# Power.net
KiCad netlist of a schematic drawn in Altium Designer
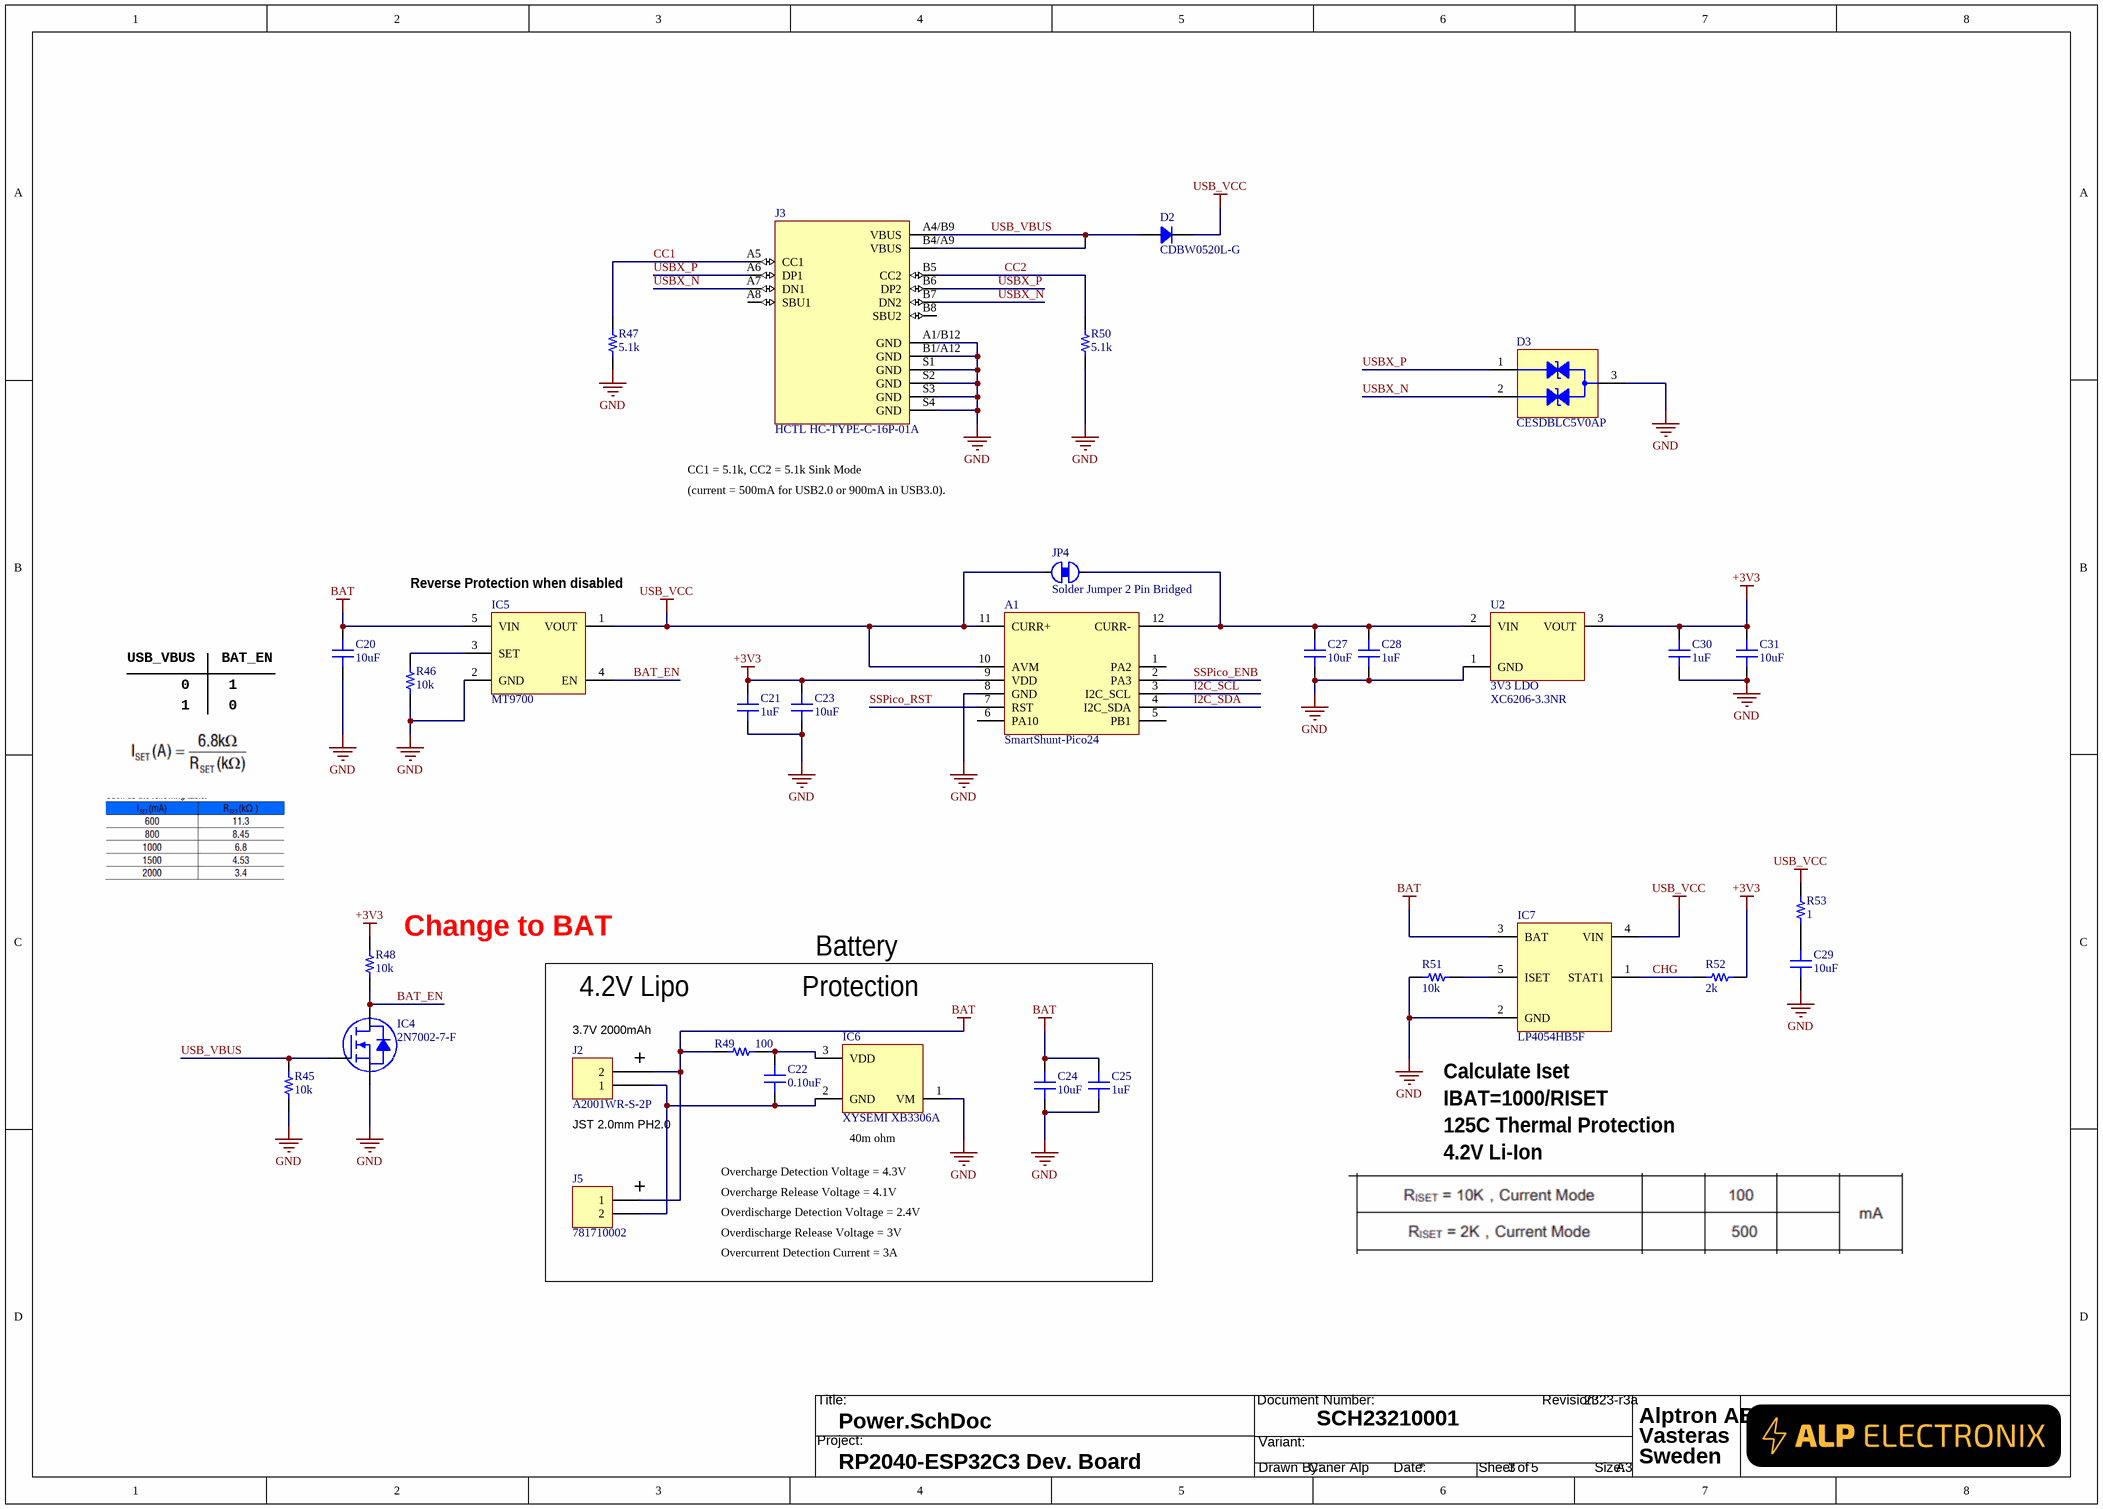
[diagram p0: Power.SchDoc]

(export (version "E")
  (design (tool "Eeschema 10.0.6"))
  (components
    (comp (ref "A1")
      (value "SmartShunt-Pico24")
      (footprint "RP2040_ESP32-C3 Dev Board PCB Lib:SmartShunt-Pico24")
      (description "Current Measurement Module")
      (libsource (lib "RP2040_ESP32-C3 Dev Board SCH Lib") (part "SmartShunt-Pico24"))
    )
    (comp (ref "C20")
      (value "10uF")
      (footprint "CAP 0603/1608")
      (description "CAP CER 10UF 6.3V X5R 0603")
      (fields
        (field (name "PART NUMBER") "GRM188R60J106ME47D")
        (field (name "MANUFACTURER") "Murata Electronics North America")
      )
      (libsource (lib "Celestial Library Database") (part "Capacitor"))
    )
    (comp (ref "C21")
      (value "1uF")
      (footprint "CAP 0402/1005")
      (description "CAP CER 1UF 6.3V X7R 0402")
      (fields
        (field (name "PART NUMBER") "GRM155R70J105KA12D")
        (field (name "MANUFACTURER") "Murata Electronics North America")
      )
      (libsource (lib "Celestial Library Database") (part "Capacitor"))
    )
    (comp (ref "C22")
      (value "0.10uF")
      (footprint "CAP 0402/1005")
      (description "CAP CER 0.1UF 10V X5R 0402")
      (fields (field (name "PART NUMBER") "LMK105BJ104KV-F") (field (name "MANUFACTURER") "Taiyo Yuden"))
      (libsource (lib "Celestial Library Database") (part "Capacitor"))
    )
    (comp (ref "C23")
      (value "10uF")
      (footprint "CAP 0603/1608")
      (description "CAP CER 10UF 6.3V X5R 0603")
      (fields
        (field (name "PART NUMBER") "GRM188R60J106ME47D")
        (field (name "MANUFACTURER") "Murata Electronics North America")
      )
      (libsource (lib "Celestial Library Database") (part "Capacitor"))
    )
    (comp (ref "C24")
      (value "10uF")
      (footprint "CAP 0603/1608")
      (description "CAP CER 10UF 6.3V X5R 0603")
      (fields
        (field (name "PART NUMBER") "GRM188R60J106ME47D")
        (field (name "MANUFACTURER") "Murata Electronics North America")
      )
      (libsource (lib "Celestial Library Database") (part "Capacitor"))
    )
    (comp (ref "C25")
      (value "1uF")
      (footprint "CAP 0402/1005")
      (description "CAP CER 1UF 6.3V X7R 0402")
      (fields
        (field (name "PART NUMBER") "GRM155R70J105KA12D")
        (field (name "MANUFACTURER") "Murata Electronics North America")
      )
      (libsource (lib "Celestial Library Database") (part "Capacitor"))
    )
    (comp (ref "C27")
      (value "10uF")
      (footprint "CAP 0603/1608")
      (description "CAP CER 10UF 6.3V X5R 0603")
      (fields
        (field (name "PART NUMBER") "GRM188R60J106ME47D")
        (field (name "MANUFACTURER") "Murata Electronics North America")
      )
      (libsource (lib "Celestial Library Database") (part "Capacitor"))
    )
    (comp (ref "C28")
      (value "1uF")
      (footprint "CAP 0402/1005")
      (description "CAP CER 1UF 6.3V X7R 0402")
      (fields
        (field (name "PART NUMBER") "GRM155R70J105KA12D")
        (field (name "MANUFACTURER") "Murata Electronics North America")
      )
      (libsource (lib "Celestial Library Database") (part "Capacitor"))
    )
    (comp (ref "C29")
      (value "10uF")
      (footprint "CAP 0603/1608")
      (description "CAP CER 10UF 6.3V X5R 0603")
      (fields
        (field (name "PART NUMBER") "GRM188R60J106ME47D")
        (field (name "MANUFACTURER") "Murata Electronics North America")
      )
      (libsource (lib "Celestial Library Database") (part "Capacitor"))
    )
    (comp (ref "C30")
      (value "1uF")
      (footprint "CAP 0402/1005")
      (description "CAP CER 1UF 6.3V X7R 0402")
      (fields
        (field (name "PART NUMBER") "GRM155R70J105KA12D")
        (field (name "MANUFACTURER") "Murata Electronics North America")
      )
      (libsource (lib "Celestial Library Database") (part "Capacitor"))
    )
    (comp (ref "C31")
      (value "10uF")
      (footprint "CAP 0603/1608")
      (description "CAP CER 10UF 6.3V X5R 0603")
      (fields
        (field (name "PART NUMBER") "GRM188R60J106ME47D")
        (field (name "MANUFACTURER") "Murata Electronics North America")
      )
      (libsource (lib "Celestial Library Database") (part "Capacitor"))
    )
    (comp (ref "D2")
      (value "CDBW0520L-G")
      (footprint "SOD-123")
      (description "DIODE SCHOTTKY 20V 500MA SOD123")
      (fields (field (name "MANUFACTURER") "Comchip Technology"))
      (libsource (lib "Celestial Altium Library - altium_library") (part "Diode"))
    )
    (comp (ref "D3")
      (value "CESDBLC5V0AP")
      (footprint "ON SEMI SOT-23-3")
      (description "TVS DIODE 24V 44V SOT23-3")
      (fields (field (name "MANUFACTURER") "ON Semiconductor"))
      (libsource (lib "Celestial Altium Library - altium_library") (part "ON SEMI SOT-23-3"))
    )
    (comp (ref "IC4")
      (value "2N7002-7-F")
      (footprint "DIODES SOT-23-3")
      (description "MOSFET N-CH 60V 115MA SOT23-3")
      (fields (field (name "MANUFACTURER") "Diodes Incorporated"))
      (libsource (lib "Celestial Library Database") (part "DIODES INC MOSFET N-CH SOT-23-3"))
    )
    (comp (ref "IC5")
      (value "MT9700")
      (footprint "RP2040_ESP32-C3 Dev Board PCB Lib:DIODES SOT-23-5 W5")
      (description "SOT-23-5 Power Distribution Switches ROHS")
      (libsource (lib "RP2040_ESP32-C3 Dev Board SCH Lib") (part "MT9700"))
    )
    (comp (ref "IC6")
      (value "XYSEMI XB3306A")
      (footprint "DIODES SOT-23-3")
      (description "IC LITHIUM BATT PROTECT SOT23-3")
      (fields (field (name "MANUFACTURER") "XYSEMI"))
      (libsource (lib "Celestial Library Database") (part "XYSEMI XB3306A"))
    )
    (comp (ref "IC7")
      (value "LP4054HB5F")
      (footprint "RP2040_ESP32-C3 Dev Board PCB Lib:DIODES SOT-23-5 W5")
      (description "600mA Standalone Linear Li-Ion Battery Charger")
      (libsource (lib "RP2040_ESP32-C3 Dev Board SCH Lib") (part "LP4054HB5F"))
    )
    (comp (ref "J2")
      (value "A2001WR-S-2P")
      (footprint "JST S2B-PH-SM4-TB")
      (description "CONN HEADER SMD R/A 2POS 2MM")
      (fields
        (field (name "PART NUMBER") "S2B-PH-SM4-TB(LF)(SN)")
        (field (name "MANUFACTURER") "JST Sales America Inc.")
      )
      (libsource (lib "Celestial Altium Library - altium_library") (part "2 Pin"))
    )
    (comp (ref "J3")
      (value "HCTL HC-TYPE-C-16P-01A")
      (footprint "RP2040_ESP32-C3 Dev Board PCB Lib:HCTL HC-TYPE-C-16P-01A")
      (description "CONN USB 2.0 TYPE-C R/A SMT")
      (fields (field (name "MANUFACTURER") "Hiro"))
      (libsource (lib "Celestial Library Database") (part "USB4110-GF-A"))
    )
    (comp (ref "J5")
      (value "781710002")
      (footprint "RP2040_ESP32-C3 Dev Board PCB Lib:Molex 781710002")
      (fields (field (name "MANUFACTURER") "Molex") (field (name "MANUFACTURER PART NUMBER") "78171-0002"))
      (libsource (lib "Miscellaneous Connectors") (part "Header 2"))
    )
    (comp (ref "JP4")
      (value "Solder Jumper 2 Pin Bridged")
      (footprint "Jumper:SolderJumper-2_P1.3mm_Bridged_RoundedPad1.0x1.5mm")
      (libsource (lib "Jumper") (part "SolderJumper_2_Bridged"))
    )
    (comp (ref "R45")
      (value "10k")
      (footprint "RES 0402/1005")
      (description "RES SMD 10K OHM 5% 1/16W 0402")
      (fields (field (name "PART NUMBER") "RC0402JR-0710KL") (field (name "MANUFACTURER") "Yageo"))
      (libsource (lib "Celestial Library Database") (part "Resistor"))
    )
    (comp (ref "R46")
      (value "10k")
      (footprint "RES 0603/1608")
      (description "RES SMD 10K OHM 5% 1/10W 0603")
      (fields
        (field (name "PART NUMBER") "ERJ-3GEYJ103V")
        (field (name "MANUFACTURER") "Panasonic Electronic Components")
      )
      (libsource (lib "Celestial Library Database") (part "Resistor"))
    )
    (comp (ref "R47")
      (value "5.1k")
      (footprint "RES 0402/1005")
      (description "RES SMD 5.1K OHM 5% 1/16W 0402")
      (fields (field (name "PART NUMBER") "RC0402JR-075K1L") (field (name "MANUFACTURER") "Yageo"))
      (libsource (lib "Celestial Library Database") (part "Resistor"))
    )
    (comp (ref "R48")
      (value "10k")
      (footprint "RES 0402/1005")
      (description "RES SMD 10K OHM 5% 1/16W 0402")
      (fields (field (name "PART NUMBER") "RC0402JR-0710KL") (field (name "MANUFACTURER") "Yageo"))
      (libsource (lib "Celestial Library Database") (part "Resistor"))
    )
    (comp (ref "R49")
      (value "100")
      (footprint "RES 0402/1005")
      (description "RES SMD 100 OHM 5% 1/16W 0402")
      (fields (field (name "PART NUMBER") "RC0402JR-07100RL") (field (name "MANUFACTURER") "Yageo"))
      (libsource (lib "Celestial Library Database") (part "Resistor"))
    )
    (comp (ref "R50")
      (value "5.1k")
      (footprint "RES 0402/1005")
      (description "RES SMD 5.1K OHM 5% 1/16W 0402")
      (fields (field (name "PART NUMBER") "RC0402JR-075K1L") (field (name "MANUFACTURER") "Yageo"))
      (libsource (lib "Celestial Library Database") (part "Resistor"))
    )
    (comp (ref "R51")
      (value "10k")
      (footprint "RES 0603/1608")
      (description "RES SMD 10K OHM 5% 1/10W 0603")
      (fields
        (field (name "PART NUMBER") "ERJ-3GEYJ103V")
        (field (name "MANUFACTURER") "Panasonic Electronic Components")
      )
      (libsource (lib "Celestial Library Database") (part "Resistor"))
    )
    (comp (ref "R52")
      (value "2k")
      (footprint "RES 0402/1005")
      (description "RES SMD 2K OHM 5% 1/16W 0402")
      (fields (field (name "PART NUMBER") "RC0402JR-072KL") (field (name "MANUFACTURER") "Yageo"))
      (libsource (lib "Celestial Library Database") (part "Resistor"))
    )
    (comp (ref "R53")
      (value "1")
      (footprint "RES 0402/1005")
      (description "RES SMD 1 OHM 5% 1/16W 0402")
      (fields (field (name "PART NUMBER") "RC0402JR-071RL") (field (name "MANUFACTURER") "Yageo"))
      (libsource (lib "Celestial Library Database") (part "Resistor"))
    )
    (comp (ref "U2")
      (value "3V3 LDO")
      (footprint "RP2040_ESP32-C3 Dev Board PCB Lib:DIODES SOT-23-3")
      (fields (field (name "MPN") "XC6206-3.3NR"))
      (libsource (lib "RP2040_ESP32-C3 Dev Board SCH Lib") (part "XC6206-3.3NR"))
    )
  )
  (nets
    (net (code "1") (name "+3V3") (class "Default")
      (node (ref "A1") (pin "9") (pinfunction "VDD_9") (pintype "passive"))
      (node (ref "C21") (pin "2") (pinfunction "2_2") (pintype "passive"))
      (node (ref "C23") (pin "2") (pinfunction "2_2") (pintype "passive"))
      (node (ref "C30") (pin "2") (pinfunction "2_2") (pintype "passive"))
      (node (ref "C31") (pin "2") (pinfunction "2_2") (pintype "passive"))
      (node (ref "R48") (pin "2") (pinfunction "2_2") (pintype "passive"))
      (node (ref "R52") (pin "2") (pinfunction "2_2") (pintype "passive"))
      (node (ref "U2") (pin "3") (pinfunction "VOUT_3") (pintype "passive"))
    )
    (net (code "2") (name "/BAT_EN") (class "Default")
      (node (ref "IC4") (pin "2") (pinfunction "D_2") (pintype "passive"))
      (node (ref "IC5") (pin "4") (pinfunction "EN_4") (pintype "passive"))
      (node (ref "R48") (pin "1") (pinfunction "1_1") (pintype "passive"))
    )
    (net (code "3") (name "/CC1") (class "Default")
      (node (ref "J3") (pin "A5") (pinfunction "CC1_A5") (pintype "bidirectional"))
      (node (ref "R47") (pin "2") (pinfunction "2_2") (pintype "passive"))
    )
    (net (code "4") (name "/CC2") (class "Default")
      (node (ref "J3") (pin "B5") (pinfunction "CC2_B5") (pintype "bidirectional"))
      (node (ref "R50") (pin "2") (pinfunction "2_2") (pintype "passive"))
    )
    (net (code "5") (name "/CHG") (class "Default")
      (node (ref "IC7") (pin "1") (pinfunction "STAT1_1") (pintype "passive"))
      (node (ref "R52") (pin "1") (pinfunction "1_1") (pintype "passive"))
    )
    (net (code "6") (name "/I2C_SCL") (class "Default")
      (node (ref "A1") (pin "3") (pinfunction "I2C_SCL_3") (pintype "passive"))
    )
    (net (code "7") (name "/I2C_SDA") (class "Default")
      (node (ref "A1") (pin "4") (pinfunction "I2C_SDA_4") (pintype "passive"))
    )
    (net (code "8") (name "/SSPico_ENB") (class "Default")
      (node (ref "A1") (pin "2") (pinfunction "PA3_2") (pintype "passive"))
    )
    (net (code "9") (name "/SSPico_RST") (class "Default")
      (node (ref "A1") (pin "7") (pinfunction "RST_7") (pintype "passive"))
    )
    (net (code "10") (name "/USBX_N") (class "Default")
      (node (ref "D3") (pin "2") (pinfunction "GND_2") (pintype "passive"))
      (node (ref "J3") (pin "A7") (pinfunction "DN1_A7") (pintype "bidirectional"))
      (node (ref "J3") (pin "B7") (pinfunction "DN2_B7") (pintype "bidirectional"))
    )
    (net (code "11") (name "/USBX_P") (class "Default")
      (node (ref "D3") (pin "1") (pinfunction "I/O_1_1") (pintype "passive"))
      (node (ref "J3") (pin "A6") (pinfunction "DP1_A6") (pintype "bidirectional"))
      (node (ref "J3") (pin "B6") (pinfunction "DP2_B6") (pintype "bidirectional"))
    )
    (net (code "12") (name "/USB_VBUS") (class "Default")
      (node (ref "D2") (pin "1") (pinfunction "1_1") (pintype "passive"))
      (node (ref "IC4") (pin "1") (pinfunction "G_1") (pintype "passive"))
      (node (ref "J3") (pin "A4/B9") (pinfunction "VBUS_A4/B9") (pintype "power_in"))
      (node (ref "J3") (pin "B4/A9") (pinfunction "VBUS_B4/A9") (pintype "power_in"))
      (node (ref "R45") (pin "2") (pinfunction "2_2") (pintype "passive"))
    )
    (net (code "13") (name "BAT") (class "Default")
      (node (ref "C20") (pin "2") (pinfunction "2_2") (pintype "passive"))
      (node (ref "C24") (pin "2") (pinfunction "2_2") (pintype "passive"))
      (node (ref "C25") (pin "2") (pinfunction "2_2") (pintype "passive"))
      (node (ref "IC5") (pin "5") (pinfunction "VIN_5") (pintype "passive"))
      (node (ref "IC7") (pin "3") (pinfunction "BAT_3") (pintype "passive"))
      (node (ref "J2") (pin "2") (pinfunction "2_2") (pintype "passive"))
      (node (ref "J5") (pin "1") (pinfunction "1_1") (pintype "passive"))
      (node (ref "R49") (pin "1") (pinfunction "1_1") (pintype "passive"))
    )
    (net (code "14") (name "GND") (class "Default")
      (node (ref "A1") (pin "8") (pinfunction "GND_8") (pintype "passive"))
      (node (ref "C20") (pin "1") (pinfunction "1_1") (pintype "passive"))
      (node (ref "C21") (pin "1") (pinfunction "1_1") (pintype "passive"))
      (node (ref "C23") (pin "1") (pinfunction "1_1") (pintype "passive"))
      (node (ref "C24") (pin "1") (pinfunction "1_1") (pintype "passive"))
      (node (ref "C25") (pin "1") (pinfunction "1_1") (pintype "passive"))
      (node (ref "C27") (pin "1") (pinfunction "1_1") (pintype "passive"))
      (node (ref "C28") (pin "1") (pinfunction "1_1") (pintype "passive"))
      (node (ref "C29") (pin "1") (pinfunction "1_1") (pintype "passive"))
      (node (ref "C30") (pin "1") (pinfunction "1_1") (pintype "passive"))
      (node (ref "C31") (pin "1") (pinfunction "1_1") (pintype "passive"))
      (node (ref "D3") (pin "3") (pinfunction "I/O_2_3") (pintype "passive"))
      (node (ref "IC4") (pin "3") (pinfunction "S_3") (pintype "passive"))
      (node (ref "IC5") (pin "2") (pinfunction "GND_2") (pintype "passive"))
      (node (ref "IC6") (pin "1") (pinfunction "VM_1") (pintype "passive"))
      (node (ref "IC7") (pin "2") (pinfunction "GND_2") (pintype "passive"))
      (node (ref "J3") (pin "A1/B12") (pinfunction "GND_A1/B12") (pintype "power_in"))
      (node (ref "J3") (pin "B1/A12") (pinfunction "GND_B1/A12") (pintype "power_in"))
      (node (ref "J3") (pin "S1") (pinfunction "GND_S1") (pintype "power_in"))
      (node (ref "J3") (pin "S2") (pinfunction "GND_S2") (pintype "power_in"))
      (node (ref "J3") (pin "S3") (pinfunction "GND_S3") (pintype "power_in"))
      (node (ref "J3") (pin "S4") (pinfunction "GND_S4") (pintype "power_in"))
      (node (ref "R45") (pin "1") (pinfunction "1_1") (pintype "passive"))
      (node (ref "R46") (pin "1") (pinfunction "1_1") (pintype "passive"))
      (node (ref "R47") (pin "1") (pinfunction "1_1") (pintype "passive"))
      (node (ref "R50") (pin "1") (pinfunction "1_1") (pintype "passive"))
      (node (ref "R51") (pin "1") (pinfunction "1_1") (pintype "passive"))
      (node (ref "U2") (pin "1") (pinfunction "GND_1") (pintype "passive"))
    )
    (net (code "15") (name "Net-(A1-CURR-)") (class "Default")
      (node (ref "A1") (pin "12") (pinfunction "CURR-_12") (pintype "passive"))
      (node (ref "C27") (pin "2") (pinfunction "2_2") (pintype "passive"))
      (node (ref "C28") (pin "2") (pinfunction "2_2") (pintype "passive"))
      (node (ref "JP4") (pin "2") (pinfunction "B_2") (pintype "passive"))
      (node (ref "U2") (pin "2") (pinfunction "VIN_2") (pintype "passive"))
    )
    (net (code "16") (name "Net-(C29-Pad2)") (class "Default")
      (node (ref "C29") (pin "2") (pinfunction "2_2") (pintype "passive"))
      (node (ref "R53") (pin "1") (pinfunction "1_1") (pintype "passive"))
    )
    (net (code "17") (name "Net-(IC5-SET)") (class "Default")
      (node (ref "IC5") (pin "3") (pinfunction "SET_3") (pintype "passive"))
      (node (ref "R46") (pin "2") (pinfunction "2_2") (pintype "passive"))
    )
    (net (code "18") (name "Net-(IC6-GND)") (class "Default")
      (node (ref "C22") (pin "1") (pinfunction "1_1") (pintype "passive"))
      (node (ref "IC6") (pin "2") (pinfunction "GND_2") (pintype "passive"))
      (node (ref "J2") (pin "1") (pinfunction "1_1") (pintype "passive"))
      (node (ref "J5") (pin "2") (pinfunction "2_2") (pintype "passive"))
    )
    (net (code "19") (name "Net-(IC6-VDD)") (class "Default")
      (node (ref "C22") (pin "2") (pinfunction "2_2") (pintype "passive"))
      (node (ref "IC6") (pin "3") (pinfunction "VDD_3") (pintype "passive"))
      (node (ref "R49") (pin "2") (pinfunction "2_2") (pintype "passive"))
    )
    (net (code "20") (name "Net-(IC7-ISET)") (class "Default")
      (node (ref "IC7") (pin "5") (pinfunction "ISET_5") (pintype "passive"))
      (node (ref "R51") (pin "2") (pinfunction "2_2") (pintype "passive"))
    )
    (net (code "21") (name "USB_VCC") (class "Default")
      (node (ref "A1") (pin "10") (pinfunction "AVM_10") (pintype "passive"))
      (node (ref "A1") (pin "11") (pinfunction "CURR+_11") (pintype "passive"))
      (node (ref "D2") (pin "2") (pinfunction "2_2") (pintype "passive"))
      (node (ref "IC5") (pin "1") (pinfunction "VOUT_1") (pintype "passive"))
      (node (ref "IC7") (pin "4") (pinfunction "VIN_4") (pintype "passive"))
      (node (ref "JP4") (pin "1") (pinfunction "A_1") (pintype "passive"))
      (node (ref "R53") (pin "2") (pinfunction "2_2") (pintype "passive"))
    )
    (net (code "22") (name "unconnected-(A1-PA2-Pad1)") (class "Default")
      (node (ref "A1") (pin "1") (pinfunction "PA2_1") (pintype "passive"))
    )
    (net (code "23") (name "unconnected-(A1-PA10-Pad6)") (class "Default")
      (node (ref "A1") (pin "6") (pinfunction "PA10_6") (pintype "passive"))
    )
    (net (code "24") (name "unconnected-(A1-PB1-Pad5)") (class "Default")
      (node (ref "A1") (pin "5") (pinfunction "PB1_5") (pintype "passive"))
    )
    (net (code "25") (name "unconnected-(J3-SBU1-PadA8)") (class "Default")
      (node (ref "J3") (pin "A8") (pinfunction "SBU1_A8") (pintype "bidirectional"))
    )
    (net (code "26") (name "unconnected-(J3-SBU2-PadB8)") (class "Default")
      (node (ref "J3") (pin "B8") (pinfunction "SBU2_B8") (pintype "bidirectional"))
    )
  )
)
